# ESP32.net
KiCad netlist of a schematic drawn in Altium Designer
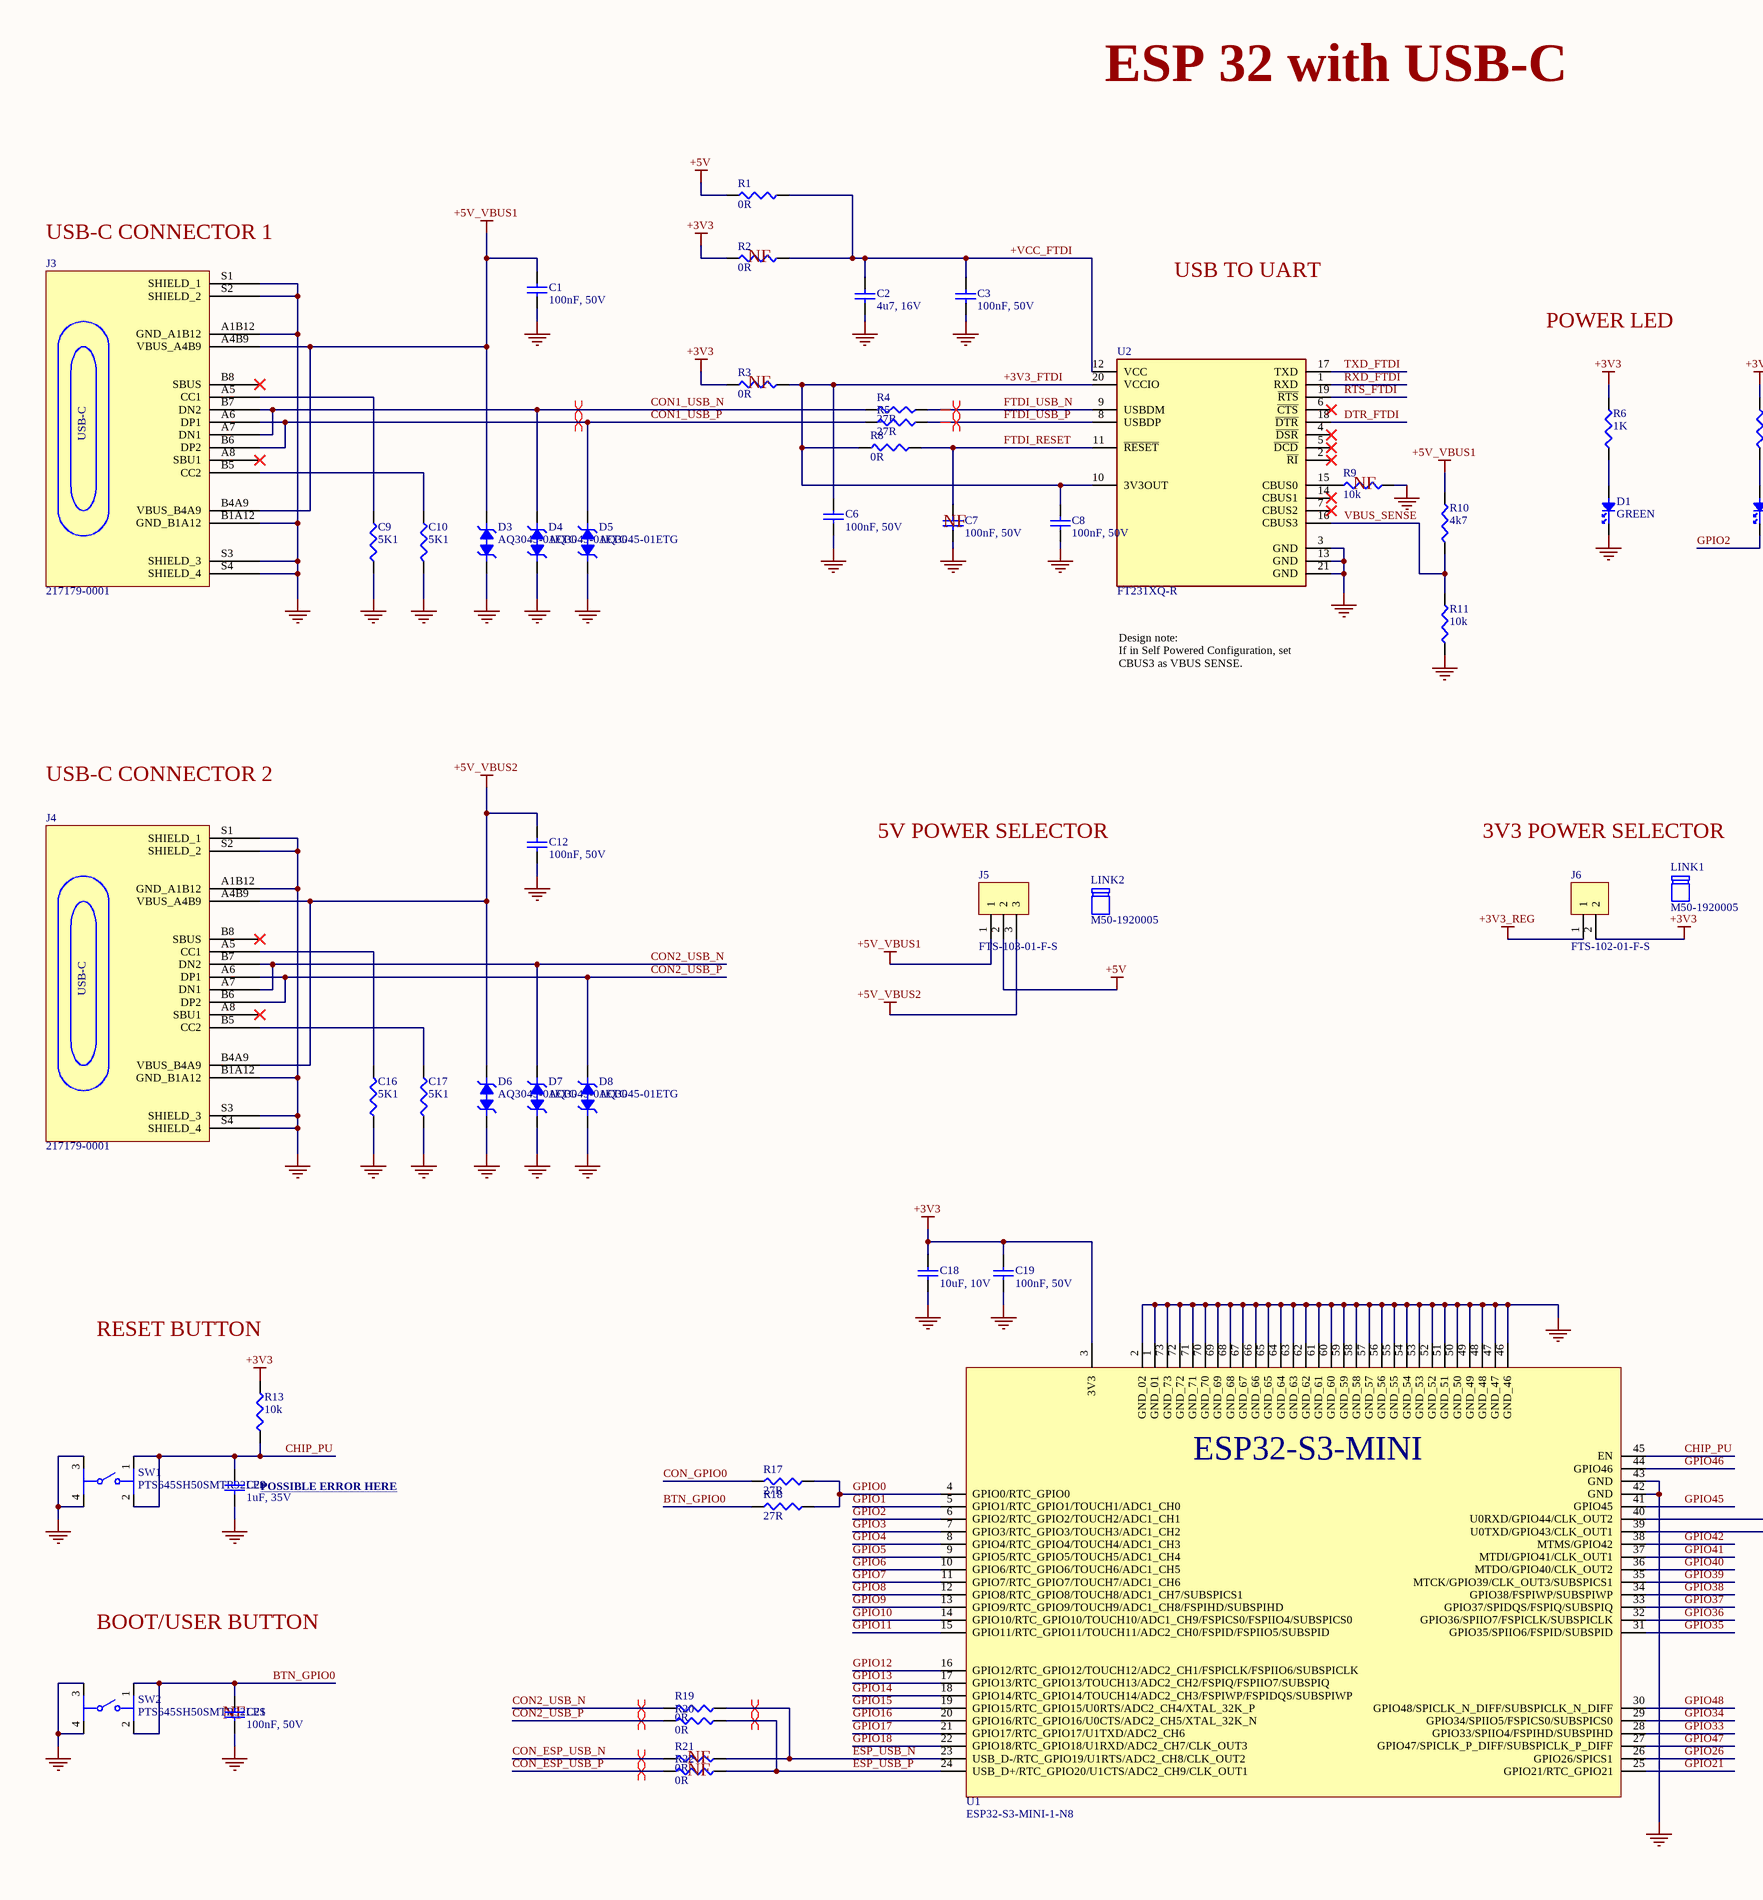
[diagram p0: ESP32.SchDoc, left]
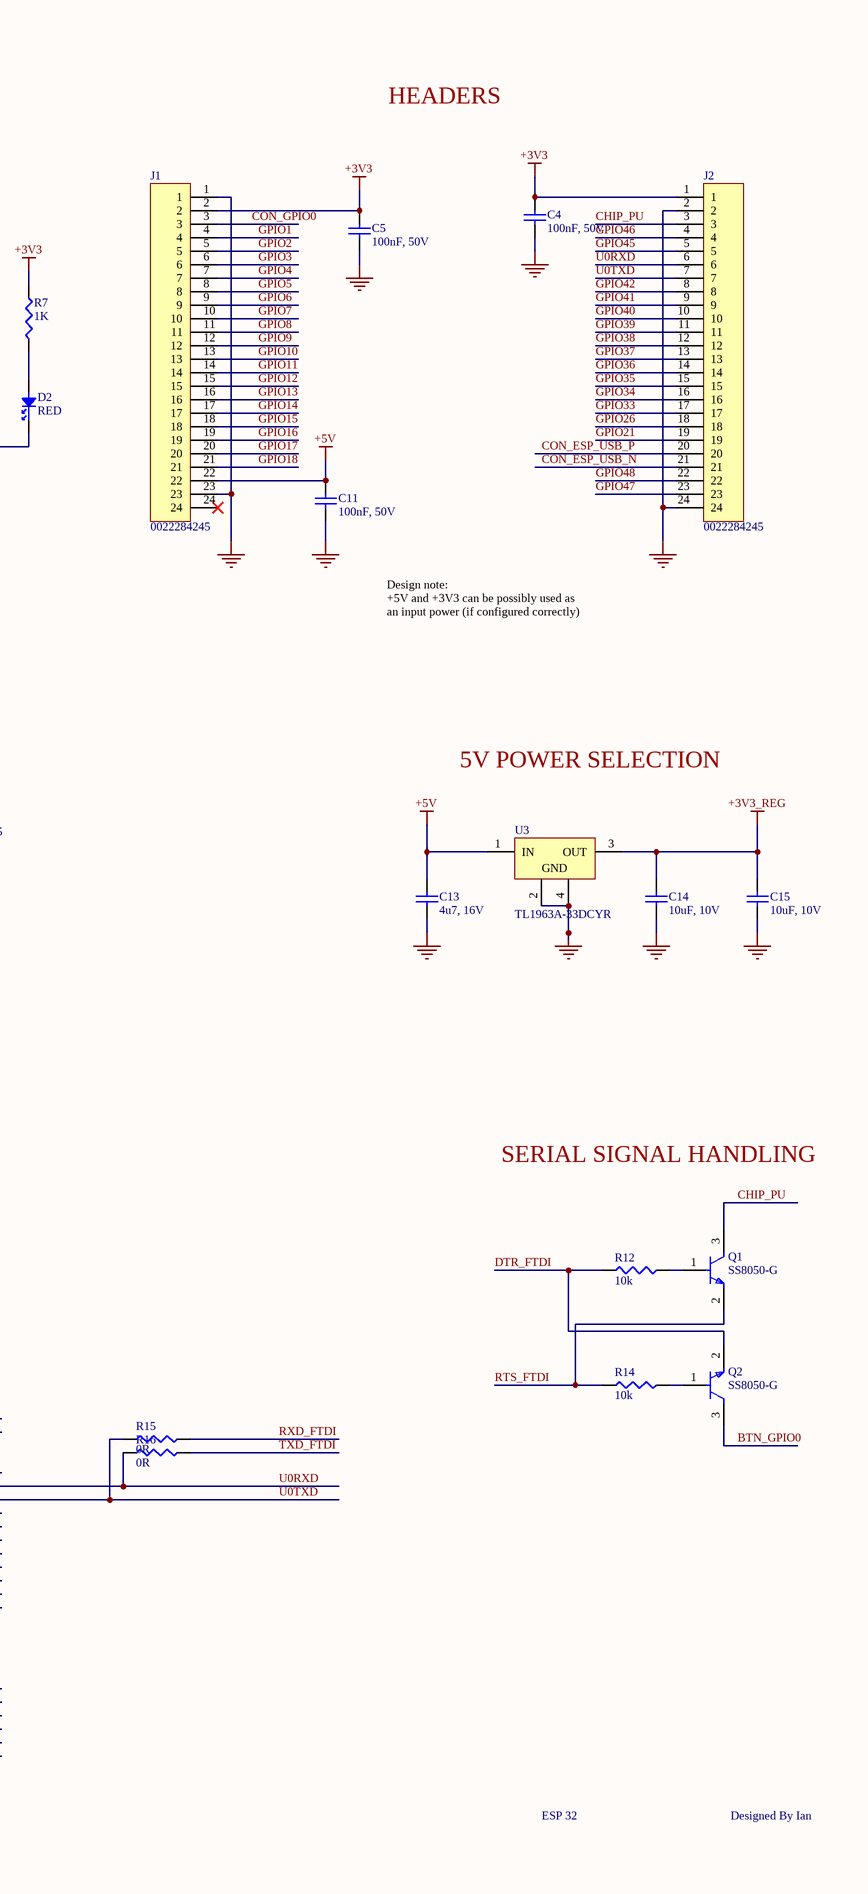
[diagram p1: ESP32.SchDoc, right]

(export (version "E")
  (design (tool "Eeschema 10.0.6"))
  (components
    (comp (ref "C1")
      (value "100nF, 50V")
      (footprint "CAPC1005X55N")
      (description "CAP CER 0.1UF 50V X7R 0402")
      (fields
        (field (name "MANUFACTURER") "Samsung")
        (field (name "MANUFACTURER PART NUMBER") "CL05B104KB54PNC")
      )
      (libsource (lib "Schlib1") (part "CL05B104KB54PNC"))
    )
    (comp (ref "C2")
      (value "4u7, 16V")
      (footprint "CAPC1005X55N")
      (description "CAP CER 4.7UF 16V X5R 0402")
      (fields
        (field (name "MANUFACTURER") "Samsung")
        (field (name "MANUFACTURER PART NUMBER") "CL05A475MO5NUNC")
      )
      (libsource (lib "Schlib1") (part "CL05A475MO5NUNC"))
    )
    (comp (ref "C3")
      (value "100nF, 50V")
      (footprint "CAPC1005X55N")
      (description "CAP CER 0.1UF 50V X7R 0402")
      (fields
        (field (name "MANUFACTURER") "Samsung")
        (field (name "MANUFACTURER PART NUMBER") "CL05B104KB54PNC")
      )
      (libsource (lib "Schlib1") (part "CL05B104KB54PNC"))
    )
    (comp (ref "C4")
      (value "100nF, 50V")
      (footprint "CAPC1005X55N")
      (description "CAP CER 0.1UF 50V X7R 0402")
      (fields
        (field (name "MANUFACTURER") "Samsung")
        (field (name "MANUFACTURER PART NUMBER") "CL05B104KB54PNC")
      )
      (libsource (lib "Schlib1") (part "CL05B104KB54PNC"))
    )
    (comp (ref "C5")
      (value "100nF, 50V")
      (footprint "CAPC1005X55N")
      (description "CAP CER 0.1UF 50V X7R 0402")
      (fields
        (field (name "MANUFACTURER") "Samsung")
        (field (name "MANUFACTURER PART NUMBER") "CL05B104KB54PNC")
      )
      (libsource (lib "Schlib1") (part "CL05B104KB54PNC"))
    )
    (comp (ref "C6")
      (value "100nF, 50V")
      (footprint "CAPC1005X55N")
      (description "CAP CER 0.1UF 50V X7R 0402")
      (fields
        (field (name "MANUFACTURER") "Samsung")
        (field (name "MANUFACTURER PART NUMBER") "CL05B104KB54PNC")
      )
      (libsource (lib "Schlib1") (part "CL05B104KB54PNC"))
    )
    (comp (ref "C7")
      (value "100nF, 50V")
      (footprint "CAPC1005X55N")
      (description "CAP CER 0.1UF 50V X7R 0402")
      (fields
        (field (name "MANUFACTURER") "Samsung")
        (field (name "MANUFACTURER PART NUMBER") "CL05B104KB54PNC")
      )
      (libsource (lib "Schlib1") (part "CL05B104KB54PNC"))
    )
    (comp (ref "C8")
      (value "100nF, 50V")
      (footprint "CAPC1005X55N")
      (description "CAP CER 0.1UF 50V X7R 0402")
      (fields
        (field (name "MANUFACTURER") "Samsung")
        (field (name "MANUFACTURER PART NUMBER") "CL05B104KB54PNC")
      )
      (libsource (lib "Schlib1") (part "CL05B104KB54PNC"))
    )
    (comp (ref "C9")
      (value "5K1")
      (footprint "RESC1005X37N")
      (description "5.1 kOhms ±1% 0.063W, 1/16W Chip Resistor 0402")
      (fields
        (field (name "MANUFACTURER") "Yageo")
        (field (name "MANUFACTURER PART NUMBER") "AC0402FR-075K1L")
      )
      (libsource (lib "Schlib1") (part "AC0402FR-075K1L"))
    )
    (comp (ref "C10")
      (value "5K1")
      (footprint "RESC1005X37N")
      (description "5.1 kOhms ±1% 0.063W, 1/16W Chip Resistor 0402")
      (fields
        (field (name "MANUFACTURER") "Yageo")
        (field (name "MANUFACTURER PART NUMBER") "AC0402FR-075K1L")
      )
      (libsource (lib "Schlib1") (part "AC0402FR-075K1L"))
    )
    (comp (ref "C11")
      (value "100nF, 50V")
      (footprint "CAPC1005X55N")
      (description "CAP CER 0.1UF 50V X7R 0402")
      (fields
        (field (name "MANUFACTURER") "Samsung")
        (field (name "MANUFACTURER PART NUMBER") "CL05B104KB54PNC")
      )
      (libsource (lib "Schlib1") (part "CL05B104KB54PNC"))
    )
    (comp (ref "C12")
      (value "100nF, 50V")
      (footprint "CAPC1005X55N")
      (description "CAP CER 0.1UF 50V X7R 0402")
      (fields
        (field (name "MANUFACTURER") "Samsung")
        (field (name "MANUFACTURER PART NUMBER") "CL05B104KB54PNC")
      )
      (libsource (lib "Schlib1") (part "CL05B104KB54PNC"))
    )
    (comp (ref "C13")
      (value "4u7, 16V")
      (footprint "CAPC1005X55N")
      (description "CAP CER 4.7UF 16V X5R 0402")
      (fields
        (field (name "MANUFACTURER") "Samsung")
        (field (name "MANUFACTURER PART NUMBER") "CL05A475MO5NUNC")
      )
      (libsource (lib "Schlib1") (part "CL05A475MO5NUNC"))
    )
    (comp (ref "C14")
      (value "10uF, 10V")
      (footprint "CAPC1005X55N")
      (description "CAP CER 10UF 10V X5R 0402")
      (fields
        (field (name "MANUFACTURER") "Samsung")
        (field (name "MANUFACTURER PART NUMBER") "CL05A106MP5NUNC")
      )
      (libsource (lib "Schlib1") (part "CL05A106MP5NUNC"))
    )
    (comp (ref "C15")
      (value "10uF, 10V")
      (footprint "CAPC1005X55N")
      (description "CAP CER 10UF 10V X5R 0402")
      (fields
        (field (name "MANUFACTURER") "Samsung")
        (field (name "MANUFACTURER PART NUMBER") "CL05A106MP5NUNC")
      )
      (libsource (lib "Schlib1") (part "CL05A106MP5NUNC"))
    )
    (comp (ref "C16")
      (value "5K1")
      (footprint "RESC1005X37N")
      (description "5.1 kOhms ±1% 0.063W, 1/16W Chip Resistor 0402")
      (fields
        (field (name "MANUFACTURER") "Yageo")
        (field (name "MANUFACTURER PART NUMBER") "AC0402FR-075K1L")
      )
      (libsource (lib "Schlib1") (part "AC0402FR-075K1L"))
    )
    (comp (ref "C17")
      (value "5K1")
      (footprint "RESC1005X37N")
      (description "5.1 kOhms ±1% 0.063W, 1/16W Chip Resistor 0402")
      (fields
        (field (name "MANUFACTURER") "Yageo")
        (field (name "MANUFACTURER PART NUMBER") "AC0402FR-075K1L")
      )
      (libsource (lib "Schlib1") (part "AC0402FR-075K1L"))
    )
    (comp (ref "C18")
      (value "10uF, 10V")
      (footprint "CAPC1005X55N")
      (description "CAP CER 10UF 10V X5R 0402")
      (fields
        (field (name "MANUFACTURER") "Samsung")
        (field (name "MANUFACTURER PART NUMBER") "CL05A106MP5NUNC")
      )
      (libsource (lib "Schlib1") (part "CL05A106MP5NUNC"))
    )
    (comp (ref "C19")
      (value "100nF, 50V")
      (footprint "CAPC1005X55N")
      (description "CAP CER 0.1UF 50V X7R 0402")
      (fields
        (field (name "MANUFACTURER") "Samsung")
        (field (name "MANUFACTURER PART NUMBER") "CL05B104KB54PNC")
      )
      (libsource (lib "Schlib1") (part "CL05B104KB54PNC"))
    )
    (comp (ref "C20")
      (value "1uF, 35V")
      (footprint "CAPC1005X55N")
      (description "1 µF ±10% 35V Ceramic Capacitor X5R 0402 (1005 Metric)")
      (fields
        (field (name "MANUFACTURER") "Murata")
        (field (name "MANUFACTURER PART NUMBER") "GRM155R6YA105KE11D")
      )
      (libsource (lib "Schlib1") (part "GRM155R6YA105KE11D"))
    )
    (comp (ref "C21")
      (value "100nF, 50V")
      (footprint "CAPC1005X55N")
      (description "CAP CER 0.1UF 50V X7R 0402")
      (fields
        (field (name "MANUFACTURER") "Samsung")
        (field (name "MANUFACTURER PART NUMBER") "CL05B104KB54PNC")
      )
      (libsource (lib "Schlib1") (part "CL05B104KB54PNC"))
    )
    (comp (ref "D1")
      (value "GREEN")
      (footprint "LED0402G")
      (description "LED YLW-GRN 0402 SMD")
      (fields
        (field (name "MANUFACTURER") "Vishay")
        (field (name "MANUFACTURER PART NUMBER") "VLMG1500-GS08")
      )
      (libsource (lib "Schlib1") (part "VLMG1500-GS08"))
    )
    (comp (ref "D2")
      (value "RED")
      (footprint "LED0402R")
      (description "LED RED 0402 SMD")
      (fields
        (field (name "MANUFACTURER") "Vishay")
        (field (name "MANUFACTURER PART NUMBER") "VLMS1500-GS08")
      )
      (libsource (lib "Schlib1") (part "VLMS1500-GS08"))
    )
    (comp (ref "D3")
      (value "AQ3045-01ETG")
      (footprint "SOD882")
      (description "TVS DIODE 5.3VWM 12VC SOD882")
      (fields (field (name "MANUFACTURER") "Littelfuse") (field (name "LCSC PART NUMBER") "C3710326"))
      (libsource (lib "Schlib1") (part "AQ3045-01ETG"))
    )
    (comp (ref "D4")
      (value "AQ3045-01ETG")
      (footprint "SOD882")
      (description "TVS DIODE 5.3VWM 12VC SOD882")
      (fields (field (name "MANUFACTURER") "Littelfuse") (field (name "LCSC PART NUMBER") "C3710326"))
      (libsource (lib "Schlib1") (part "AQ3045-01ETG"))
    )
    (comp (ref "D5")
      (value "AQ3045-01ETG")
      (footprint "SOD882")
      (description "TVS DIODE 5.3VWM 12VC SOD882")
      (fields (field (name "MANUFACTURER") "Littelfuse") (field (name "LCSC PART NUMBER") "C3710326"))
      (libsource (lib "Schlib1") (part "AQ3045-01ETG"))
    )
    (comp (ref "D6")
      (value "AQ3045-01ETG")
      (footprint "SOD882")
      (description "TVS DIODE 5.3VWM 12VC SOD882")
      (fields (field (name "MANUFACTURER") "Littelfuse") (field (name "LCSC PART NUMBER") "C3710326"))
      (libsource (lib "Schlib1") (part "AQ3045-01ETG"))
    )
    (comp (ref "D7")
      (value "AQ3045-01ETG")
      (footprint "SOD882")
      (description "TVS DIODE 5.3VWM 12VC SOD882")
      (fields (field (name "MANUFACTURER") "Littelfuse") (field (name "LCSC PART NUMBER") "C3710326"))
      (libsource (lib "Schlib1") (part "AQ3045-01ETG"))
    )
    (comp (ref "D8")
      (value "AQ3045-01ETG")
      (footprint "SOD882")
      (description "TVS DIODE 5.3VWM 12VC SOD882")
      (fields (field (name "MANUFACTURER") "Littelfuse") (field (name "LCSC PART NUMBER") "C3710326"))
      (libsource (lib "Schlib1") (part "AQ3045-01ETG"))
    )
    (comp (ref "J1")
      (value "0022284245")
      (footprint "HDR_1X24_2.54mm")
      (description "CONN HEADER VERT 24POS 2.54MM")
      (fields (field (name "MANUFACTURER") "Molex") (field (name "LCSC PART NUMBER") "C7145888"))
      (libsource (lib "Schlib1") (part "0022284245"))
    )
    (comp (ref "J2")
      (value "0022284245")
      (footprint "HDR_1X24_2.54mm")
      (description "CONN HEADER VERT 24POS 2.54MM")
      (fields (field (name "MANUFACTURER") "Molex") (field (name "LCSC PART NUMBER") "C7145888"))
      (libsource (lib "") (part "0022284245_1"))
    )
    (comp (ref "J3")
      (value "217179-0001")
      (footprint "FP-2171790001-MFG")
      (description "CONN RCP USB2.0 TYP C 24P SMD RA")
      (fields (field (name "MANUFACTURER") "Molex") (field (name "LCSC PART NUMBER") "C3197684"))
      (libsource (lib "Schlib1") (part "217179-0001"))
    )
    (comp (ref "J4")
      (value "217179-0001")
      (footprint "FP-2171790001-MFG")
      (description "CONN RCP USB2.0 TYP C 24P SMD RA")
      (fields (field (name "MANUFACTURER") "Molex") (field (name "LCSC PART NUMBER") "C3197684"))
      (libsource (lib "Schlib1") (part "217179-0001"))
    )
    (comp (ref "J5")
      (value "FTS-103-01-F-S")
      (footprint "HDR_1X3_1.27MM")
      (description "CONN HEADER VERT 3POS 1.27MM")
      (fields (field (name "MANUFACTURER") "Samtec") (field (name "LCSC PART NUMBER") "C3333578"))
      (libsource (lib "Schlib1") (part "FTS-103-01-F-S"))
    )
    (comp (ref "J6")
      (value "FTS-102-01-F-S")
      (footprint "HDR_1X2_1.27MM")
      (description "CONN HEADER VERT 2POS 1.27MM")
      (fields (field (name "MANUFACTURER") "Samtec") (field (name "LCSC PART NUMBER") "C6045317"))
      (libsource (lib "Schlib1") (part "FTS-102-01-F-S"))
    )
    (comp (ref "LINK1")
      (value "M50-1920005")
      (description "CONN SHUNT 1.27MM RED")
      (fields (field (name "MANUFACTURER") "Harwin") (field (name "LCSC PART NUMBER") "C6985646"))
      (libsource (lib "Schlib1") (part "M50-1920005"))
    )
    (comp (ref "LINK2")
      (value "M50-1920005")
      (description "CONN SHUNT 1.27MM RED")
      (fields (field (name "MANUFACTURER") "Harwin") (field (name "LCSC PART NUMBER") "C6985646"))
      (libsource (lib "Schlib1") (part "M50-1920005"))
    )
    (comp (ref "Q1")
      (value "SS8050-G")
      (footprint "FP-SS8050-G-IPC_B")
      (description "TRANS NPN 25V 1.5A SOT23-3")
      (fields (field (name "MANUFACTURER") "Comchip") (field (name "LCSC PART NUMBER") "C3199946"))
      (libsource (lib "Schlib1") (part "SS8050-G"))
    )
    (comp (ref "Q2")
      (value "SS8050-G")
      (footprint "FP-SS8050-G-IPC_B")
      (description "TRANS NPN 25V 1.5A SOT23-3")
      (fields (field (name "MANUFACTURER") "Comchip") (field (name "LCSC PART NUMBER") "C3199946"))
      (libsource (lib "Schlib1") (part "SS8050-G"))
    )
    (comp (ref "R1")
      (value "0R")
      (footprint "RESC1005X37N")
      (description "RES 0 OHM JUMPER 1/16W 0402")
      (fields
        (field (name "MANUFACTURER") "Yageo")
        (field (name "MANUFACTURER PART NUMBER") "RC0402JR-070RL")
      )
      (libsource (lib "Schlib1") (part "RC0402JR-070RL"))
    )
    (comp (ref "R2")
      (value "0R")
      (footprint "RESC1005X37N")
      (description "RES 0 OHM JUMPER 1/16W 0402")
      (fields
        (field (name "MANUFACTURER") "Yageo")
        (field (name "MANUFACTURER PART NUMBER") "RC0402JR-070RL")
      )
      (libsource (lib "Schlib1") (part "RC0402JR-070RL"))
    )
    (comp (ref "R3")
      (value "0R")
      (footprint "RESC1005X37N")
      (description "RES 0 OHM JUMPER 1/16W 0402")
      (fields
        (field (name "MANUFACTURER") "Yageo")
        (field (name "MANUFACTURER PART NUMBER") "RC0402JR-070RL")
      )
      (libsource (lib "Schlib1") (part "RC0402JR-070RL"))
    )
    (comp (ref "R4")
      (value "27R")
      (footprint "RESC1005X37N")
      (description "27 Ohms ±1% 0.063W, 1/16W Chip Resistor 0402")
      (fields
        (field (name "MANUFACTURER") "Yageo")
        (field (name "MANUFACTURER PART NUMBER") "RC0402FR-0727RL")
      )
      (libsource (lib "Schlib1") (part "RC0402FR-0727RL"))
    )
    (comp (ref "R5")
      (value "27R")
      (footprint "RESC1005X37N")
      (description "27 Ohms ±1% 0.063W, 1/16W Chip Resistor 0402")
      (fields
        (field (name "MANUFACTURER") "Yageo")
        (field (name "MANUFACTURER PART NUMBER") "RC0402FR-0727RL")
      )
      (libsource (lib "Schlib1") (part "RC0402FR-0727RL"))
    )
    (comp (ref "R6")
      (value "1K")
      (footprint "RESC1005X37N")
      (description "RES 1K OHM 1% 1/16W 0402")
      (fields
        (field (name "MANUFACTURER") "Yageo")
        (field (name "MANUFACTURER PART NUMBER") "RC0402FR-071KL")
      )
      (libsource (lib "Schlib1") (part "RC0402FR-071KL"))
    )
    (comp (ref "R7")
      (value "1K")
      (footprint "RESC1005X37N")
      (description "RES 1K OHM 1% 1/16W 0402")
      (fields
        (field (name "MANUFACTURER") "Yageo")
        (field (name "MANUFACTURER PART NUMBER") "RC0402FR-071KL")
      )
      (libsource (lib "Schlib1") (part "RC0402FR-071KL"))
    )
    (comp (ref "R8")
      (value "0R")
      (footprint "RESC1005X37N")
      (description "RES 0 OHM JUMPER 1/16W 0402")
      (fields
        (field (name "MANUFACTURER") "Yageo")
        (field (name "MANUFACTURER PART NUMBER") "RC0402JR-070RL")
      )
      (libsource (lib "Schlib1") (part "RC0402JR-070RL"))
    )
    (comp (ref "R9")
      (value "10k")
      (footprint "RESC1005X37N")
      (description "RES SMD 10K OHM 1% 1/16W 0402")
      (fields
        (field (name "MANUFACTURER") "Yageo")
        (field (name "MANUFACTURER PART NUMBER") "AC0402FR-0710KL")
      )
      (libsource (lib "Schlib1") (part "AC0402FR-0710KL"))
    )
    (comp (ref "R10")
      (value "4k7")
      (footprint "RESC1005X37N")
      (description "RES 4.7K OHM 5% 1/16W 0402")
      (fields
        (field (name "MANUFACTURER") "Yageo")
        (field (name "MANUFACTURER PART NUMBER") "RC0402JR-074K7L")
      )
      (libsource (lib "Schlib1") (part "RC0402JR-074K7L"))
    )
    (comp (ref "R11")
      (value "10k")
      (footprint "RESC1005X37N")
      (description "RES SMD 10K OHM 1% 1/16W 0402")
      (fields
        (field (name "MANUFACTURER") "Yageo")
        (field (name "MANUFACTURER PART NUMBER") "AC0402FR-0710KL")
      )
      (libsource (lib "Schlib1") (part "AC0402FR-0710KL"))
    )
    (comp (ref "R12")
      (value "10k")
      (footprint "RESC1005X37N")
      (description "RES SMD 10K OHM 1% 1/16W 0402")
      (fields
        (field (name "MANUFACTURER") "Yageo")
        (field (name "MANUFACTURER PART NUMBER") "AC0402FR-0710KL")
      )
      (libsource (lib "Schlib1") (part "AC0402FR-0710KL"))
    )
    (comp (ref "R13")
      (value "10k")
      (footprint "RESC1005X37N")
      (description "RES SMD 10K OHM 1% 1/16W 0402")
      (fields
        (field (name "MANUFACTURER") "Yageo")
        (field (name "MANUFACTURER PART NUMBER") "AC0402FR-0710KL")
      )
      (libsource (lib "Schlib1") (part "AC0402FR-0710KL"))
    )
    (comp (ref "R14")
      (value "10k")
      (footprint "RESC1005X37N")
      (description "RES SMD 10K OHM 1% 1/16W 0402")
      (fields
        (field (name "MANUFACTURER") "Yageo")
        (field (name "MANUFACTURER PART NUMBER") "AC0402FR-0710KL")
      )
      (libsource (lib "Schlib1") (part "AC0402FR-0710KL"))
    )
    (comp (ref "R15")
      (value "0R")
      (footprint "RESC1005X37N")
      (description "RES 0 OHM JUMPER 1/16W 0402")
      (fields
        (field (name "MANUFACTURER") "Yageo")
        (field (name "MANUFACTURER PART NUMBER") "RC0402JR-070RL")
      )
      (libsource (lib "Schlib1") (part "RC0402JR-070RL"))
    )
    (comp (ref "R16")
      (value "0R")
      (footprint "RESC1005X37N")
      (description "RES 0 OHM JUMPER 1/16W 0402")
      (fields
        (field (name "MANUFACTURER") "Yageo")
        (field (name "MANUFACTURER PART NUMBER") "RC0402JR-070RL")
      )
      (libsource (lib "Schlib1") (part "RC0402JR-070RL"))
    )
    (comp (ref "R17")
      (value "27R")
      (footprint "RESC1005X37N")
      (description "27 Ohms ±1% 0.063W, 1/16W Chip Resistor 0402")
      (fields
        (field (name "MANUFACTURER") "Yageo")
        (field (name "MANUFACTURER PART NUMBER") "RC0402FR-0727RL")
      )
      (libsource (lib "Schlib1") (part "RC0402FR-0727RL"))
    )
    (comp (ref "R18")
      (value "27R")
      (footprint "RESC1005X37N")
      (description "27 Ohms ±1% 0.063W, 1/16W Chip Resistor 0402")
      (fields
        (field (name "MANUFACTURER") "Yageo")
        (field (name "MANUFACTURER PART NUMBER") "RC0402FR-0727RL")
      )
      (libsource (lib "Schlib1") (part "RC0402FR-0727RL"))
    )
    (comp (ref "R19")
      (value "0R")
      (footprint "RESC1005X37N")
      (description "RES 0 OHM JUMPER 1/16W 0402")
      (fields
        (field (name "MANUFACTURER") "Yageo")
        (field (name "MANUFACTURER PART NUMBER") "RC0402JR-070RL")
      )
      (libsource (lib "Schlib1") (part "RC0402JR-070RL"))
    )
    (comp (ref "R20")
      (value "0R")
      (footprint "RESC1005X37N")
      (description "RES 0 OHM JUMPER 1/16W 0402")
      (fields
        (field (name "MANUFACTURER") "Yageo")
        (field (name "MANUFACTURER PART NUMBER") "RC0402JR-070RL")
      )
      (libsource (lib "Schlib1") (part "RC0402JR-070RL"))
    )
    (comp (ref "R21")
      (value "0R")
      (footprint "RESC1005X37N")
      (description "RES 0 OHM JUMPER 1/16W 0402")
      (fields
        (field (name "MANUFACTURER") "Yageo")
        (field (name "MANUFACTURER PART NUMBER") "RC0402JR-070RL")
      )
      (libsource (lib "Schlib1") (part "RC0402JR-070RL"))
    )
    (comp (ref "R22")
      (value "0R")
      (footprint "RESC1005X37N")
      (description "RES 0 OHM JUMPER 1/16W 0402")
      (fields
        (field (name "MANUFACTURER") "Yageo")
        (field (name "MANUFACTURER PART NUMBER") "RC0402JR-070RL")
      )
      (libsource (lib "Schlib1") (part "RC0402JR-070RL"))
    )
    (comp (ref "SW1")
      (value "PTS645SH50SMTR92LFS")
      (footprint "FP-PTS645SH50SMTR92LFS-MFG")
      (description "Tactile Switch SPST-NO Top Actuated Surface Mount")
      (fields (field (name "MANUFACTURER") "ITT C&K") (field (name "LCSC PART NUMBER") "C221869"))
      (libsource (lib "Schlib1") (part "PTS645SH50SMTR92LFS"))
    )
    (comp (ref "SW2")
      (value "PTS645SH50SMTR92LFS")
      (footprint "FP-PTS645SH50SMTR92LFS-MFG")
      (description "Tactile Switch SPST-NO Top Actuated Surface Mount")
      (fields (field (name "MANUFACTURER") "ITT C&K") (field (name "LCSC PART NUMBER") "C221869"))
      (libsource (lib "Schlib1") (part "PTS645SH50SMTR92LFS"))
    )
    (comp (ref "U1")
      (value "ESP32-S3-MINI-1-N8")
      (footprint "XCVR_ESP32-S3-MINI-1-N8")
      (description "SMD module, ESP32-S3FN8, 8 MB SPI flash, PCB antenna")
      (fields (field (name "MANUFACTURER") "Espressif Systems") (field (name "LCSC PART NUMBER") "C2913206"))
      (libsource (lib "Schlib1") (part "ESP32-S3-MINI-1-N8"))
    )
    (comp (ref "U2")
      (value "FT231XQ-R")
      (footprint "FP-QFN-20-IPC_B")
      (description "IC USB SERIAL FULL UART 20QFN")
      (fields (field (name "MANUFACTURER") "FTDI") (field (name "LCSC PART NUMBER") "C132159"))
      (libsource (lib "Schlib1") (part "FT231XQ-R"))
    )
    (comp (ref "U3")
      (value "TL1963A-33DCYR")
      (footprint "DCY0004A_N")
      (description "IC REG LINEAR 3.3V 1.5A SOT223-4")
      (fields (field (name "MANUFACTURER") "Texas Instruments") (field (name "LCSC PART NUMBER") "C181262"))
      (libsource (lib "Schlib1") (part "TL1963A-33DCYR"))
    )
  )
  (nets
    (net (code "1") (name "+3V3") (class "Default")
      (node (ref "C18") (pin "2") (pinfunction "2_2") (pintype "passive"))
      (node (ref "C19") (pin "2") (pinfunction "2_2") (pintype "passive"))
      (node (ref "C4") (pin "2") (pinfunction "2_2") (pintype "passive"))
      (node (ref "C5") (pin "2") (pinfunction "2_2") (pintype "passive"))
      (node (ref "J1") (pin "2") (pinfunction "2_2") (pintype "passive"))
      (node (ref "J2") (pin "1") (pinfunction "1_1") (pintype "passive"))
      (node (ref "J6") (pin "2") (pinfunction "2_2") (pintype "passive"))
      (node (ref "R13") (pin "2") (pinfunction "2_2") (pintype "passive"))
      (node (ref "R2") (pin "1") (pinfunction "1_1") (pintype "passive"))
      (node (ref "R3") (pin "1") (pinfunction "1_1") (pintype "passive"))
      (node (ref "R6") (pin "2") (pinfunction "2_2") (pintype "passive"))
      (node (ref "R7") (pin "2") (pinfunction "2_2") (pintype "passive"))
      (node (ref "U1") (pin "3") (pinfunction "3V3_3") (pintype "passive"))
    )
    (net (code "2") (name "+3V3_REG") (class "Default")
      (node (ref "C14") (pin "2") (pinfunction "2_2") (pintype "passive"))
      (node (ref "C15") (pin "2") (pinfunction "2_2") (pintype "passive"))
      (node (ref "J6") (pin "1") (pinfunction "1_1") (pintype "passive"))
      (node (ref "U3") (pin "3") (pinfunction "OUT_3") (pintype "power_in"))
    )
    (net (code "3") (name "+5V") (class "Default")
      (node (ref "C11") (pin "2") (pinfunction "2_2") (pintype "passive"))
      (node (ref "C13") (pin "2") (pinfunction "2_2") (pintype "passive"))
      (node (ref "J1") (pin "22") (pinfunction "22_22") (pintype "passive"))
      (node (ref "J5") (pin "2") (pinfunction "2_2") (pintype "passive"))
      (node (ref "R1") (pin "1") (pinfunction "1_1") (pintype "passive"))
      (node (ref "U3") (pin "1") (pinfunction "IN_1") (pintype "power_in"))
    )
    (net (code "4") (name "+5V_VBUS1") (class "Default")
      (node (ref "C1") (pin "2") (pinfunction "2_2") (pintype "passive"))
      (node (ref "D3") (pin "2") (pinfunction "2_2") (pintype "passive"))
      (node (ref "J3") (pin "A4B9") (pinfunction "VBUS_A4B9_A4B9") (pintype "passive"))
      (node (ref "J3") (pin "B4A9") (pinfunction "VBUS_B4A9_B4A9") (pintype "passive"))
      (node (ref "J5") (pin "1") (pinfunction "1_1") (pintype "passive"))
      (node (ref "R10") (pin "2") (pinfunction "2_2") (pintype "passive"))
    )
    (net (code "5") (name "+5V_VBUS2") (class "Default")
      (node (ref "C12") (pin "2") (pinfunction "2_2") (pintype "passive"))
      (node (ref "D6") (pin "2") (pinfunction "2_2") (pintype "passive"))
      (node (ref "J4") (pin "A4B9") (pinfunction "VBUS_A4B9_A4B9") (pintype "passive"))
      (node (ref "J4") (pin "B4A9") (pinfunction "VBUS_B4A9_B4A9") (pintype "passive"))
      (node (ref "J5") (pin "3") (pinfunction "3_3") (pintype "passive"))
    )
    (net (code "6") (name "/+3V3_FTDI") (class "Default")
      (node (ref "C6") (pin "2") (pinfunction "2_2") (pintype "passive"))
      (node (ref "C8") (pin "2") (pinfunction "2_2") (pintype "passive"))
      (node (ref "R3") (pin "2") (pinfunction "2_2") (pintype "passive"))
      (node (ref "R8") (pin "1") (pinfunction "1_1") (pintype "passive"))
      (node (ref "U2") (pin "10") (pinfunction "3V3OUT_10") (pintype "passive"))
      (node (ref "U2") (pin "20") (pinfunction "VCCIO_20") (pintype "passive"))
    )
    (net (code "7") (name "/+VCC_FTDI") (class "Default")
      (node (ref "C2") (pin "2") (pinfunction "2_2") (pintype "passive"))
      (node (ref "C3") (pin "2") (pinfunction "2_2") (pintype "passive"))
      (node (ref "R1") (pin "2") (pinfunction "2_2") (pintype "passive"))
      (node (ref "R2") (pin "2") (pinfunction "2_2") (pintype "passive"))
      (node (ref "U2") (pin "12") (pinfunction "VCC_12") (pintype "passive"))
    )
    (net (code "8") (name "/BTN_GPIO0") (class "Default")
      (node (ref "C21") (pin "2") (pinfunction "2_2") (pintype "passive"))
      (node (ref "Q2") (pin "3") (pinfunction "C_3") (pintype "passive"))
      (node (ref "R18") (pin "1") (pinfunction "1_1") (pintype "passive"))
      (node (ref "SW2") (pin "1") (pinfunction "1_1") (pintype "passive"))
      (node (ref "SW2") (pin "2") (pinfunction "2_2") (pintype "passive"))
    )
    (net (code "9") (name "/CHIP_PU") (class "Default")
      (node (ref "C20") (pin "2") (pinfunction "2_2") (pintype "passive"))
      (node (ref "J2") (pin "3") (pinfunction "3_3") (pintype "passive"))
      (node (ref "Q1") (pin "3") (pinfunction "C_3") (pintype "passive"))
      (node (ref "R13") (pin "1") (pinfunction "1_1") (pintype "passive"))
      (node (ref "SW1") (pin "1") (pinfunction "1_1") (pintype "passive"))
      (node (ref "SW1") (pin "2") (pinfunction "2_2") (pintype "passive"))
      (node (ref "U1") (pin "45") (pinfunction "EN_45") (pintype "passive"))
    )
    (net (code "10") (name "/CON1_USB_N") (class "Default")
      (node (ref "D4") (pin "2") (pinfunction "2_2") (pintype "passive"))
      (node (ref "J3") (pin "A7") (pinfunction "DN1_A7") (pintype "passive"))
      (node (ref "J3") (pin "B7") (pinfunction "DN2_B7") (pintype "passive"))
      (node (ref "R4") (pin "1") (pinfunction "1_1") (pintype "passive"))
    )
    (net (code "11") (name "/CON1_USB_P") (class "Default")
      (node (ref "D5") (pin "2") (pinfunction "2_2") (pintype "passive"))
      (node (ref "J3") (pin "A6") (pinfunction "DP1_A6") (pintype "passive"))
      (node (ref "J3") (pin "B6") (pinfunction "DP2_B6") (pintype "passive"))
      (node (ref "R5") (pin "1") (pinfunction "1_1") (pintype "passive"))
    )
    (net (code "12") (name "/CON2_USB_N") (class "Default")
      (node (ref "D7") (pin "2") (pinfunction "2_2") (pintype "passive"))
      (node (ref "J4") (pin "A7") (pinfunction "DN1_A7") (pintype "passive"))
      (node (ref "J4") (pin "B7") (pinfunction "DN2_B7") (pintype "passive"))
      (node (ref "R19") (pin "1") (pinfunction "1_1") (pintype "passive"))
    )
    (net (code "13") (name "/CON2_USB_P") (class "Default")
      (node (ref "D8") (pin "2") (pinfunction "2_2") (pintype "passive"))
      (node (ref "J4") (pin "A6") (pinfunction "DP1_A6") (pintype "passive"))
      (node (ref "J4") (pin "B6") (pinfunction "DP2_B6") (pintype "passive"))
      (node (ref "R20") (pin "1") (pinfunction "1_1") (pintype "passive"))
    )
    (net (code "14") (name "/CON_ESP_USB_N") (class "Default")
      (node (ref "J2") (pin "21") (pinfunction "21_21") (pintype "passive"))
      (node (ref "R21") (pin "1") (pinfunction "1_1") (pintype "passive"))
    )
    (net (code "15") (name "/CON_ESP_USB_P") (class "Default")
      (node (ref "J2") (pin "20") (pinfunction "20_20") (pintype "passive"))
      (node (ref "R22") (pin "1") (pinfunction "1_1") (pintype "passive"))
    )
    (net (code "16") (name "/CON_GPIO0") (class "Default")
      (node (ref "J1") (pin "3") (pinfunction "3_3") (pintype "passive"))
      (node (ref "R17") (pin "1") (pinfunction "1_1") (pintype "passive"))
    )
    (net (code "17") (name "/DTR_FTDI") (class "Default")
      (node (ref "Q2") (pin "2") (pinfunction "E_2") (pintype "passive"))
      (node (ref "R12") (pin "2") (pinfunction "2_2") (pintype "passive"))
      (node (ref "U2") (pin "18") (pinfunction "~{DTR}_18") (pintype "passive"))
    )
    (net (code "18") (name "/ESP_USB_N") (class "Default")
      (node (ref "R19") (pin "2") (pinfunction "2_2") (pintype "passive"))
      (node (ref "R21") (pin "2") (pinfunction "2_2") (pintype "passive"))
      (node (ref "U1") (pin "23") (pinfunction "USB_D-/RTC_GPIO19/U1RTS/ADC2_CH8/CLK_OUT2_23") (pintype "passive"))
    )
    (net (code "19") (name "/ESP_USB_P") (class "Default")
      (node (ref "R20") (pin "2") (pinfunction "2_2") (pintype "passive"))
      (node (ref "R22") (pin "2") (pinfunction "2_2") (pintype "passive"))
      (node (ref "U1") (pin "24") (pinfunction "USB_D+/RTC_GPIO20/U1CTS/ADC2_CH9/CLK_OUT1_24") (pintype "passive"))
    )
    (net (code "20") (name "/FTDI_RESET") (class "Default")
      (node (ref "C7") (pin "2") (pinfunction "2_2") (pintype "passive"))
      (node (ref "R8") (pin "2") (pinfunction "2_2") (pintype "passive"))
      (node (ref "U2") (pin "11") (pinfunction "~{RESET}_11") (pintype "passive"))
    )
    (net (code "21") (name "/FTDI_USB_N") (class "Default")
      (node (ref "R4") (pin "2") (pinfunction "2_2") (pintype "passive"))
      (node (ref "U2") (pin "9") (pinfunction "USBDM_9") (pintype "passive"))
    )
    (net (code "22") (name "/FTDI_USB_P") (class "Default")
      (node (ref "R5") (pin "2") (pinfunction "2_2") (pintype "passive"))
      (node (ref "U2") (pin "8") (pinfunction "USBDP_8") (pintype "passive"))
    )
    (net (code "23") (name "/GPIO0") (class "Default")
      (node (ref "R17") (pin "2") (pinfunction "2_2") (pintype "passive"))
      (node (ref "R18") (pin "2") (pinfunction "2_2") (pintype "passive"))
      (node (ref "U1") (pin "4") (pinfunction "GPIO0/RTC_GPIO0_4") (pintype "passive"))
    )
    (net (code "24") (name "/GPIO1") (class "Default")
      (node (ref "J1") (pin "4") (pinfunction "4_4") (pintype "passive"))
      (node (ref "U1") (pin "5") (pinfunction "GPIO1/RTC_GPIO1/TOUCH1/ADC1_CH0_5") (pintype "passive"))
    )
    (net (code "25") (name "/GPIO2") (class "Default")
      (node (ref "D2") (pin "1") (pinfunction "1_1") (pintype "passive"))
      (node (ref "J1") (pin "5") (pinfunction "5_5") (pintype "passive"))
      (node (ref "U1") (pin "6") (pinfunction "GPIO2/RTC_GPIO2/TOUCH2/ADC1_CH1_6") (pintype "passive"))
    )
    (net (code "26") (name "/GPIO3") (class "Default")
      (node (ref "J1") (pin "6") (pinfunction "6_6") (pintype "passive"))
      (node (ref "U1") (pin "7") (pinfunction "GPIO3/RTC_GPIO3/TOUCH3/ADC1_CH2_7") (pintype "passive"))
    )
    (net (code "27") (name "/GPIO4") (class "Default")
      (node (ref "J1") (pin "7") (pinfunction "7_7") (pintype "passive"))
      (node (ref "U1") (pin "8") (pinfunction "GPIO4/RTC_GPIO4/TOUCH4/ADC1_CH3_8") (pintype "passive"))
    )
    (net (code "28") (name "/GPIO5") (class "Default")
      (node (ref "J1") (pin "8") (pinfunction "8_8") (pintype "passive"))
      (node (ref "U1") (pin "9") (pinfunction "GPIO5/RTC_GPIO5/TOUCH5/ADC1_CH4_9") (pintype "passive"))
    )
    (net (code "29") (name "/GPIO6") (class "Default")
      (node (ref "J1") (pin "9") (pinfunction "9_9") (pintype "passive"))
      (node (ref "U1") (pin "10") (pinfunction "GPIO6/RTC_GPIO6/TOUCH6/ADC1_CH5_10") (pintype "passive"))
    )
    (net (code "30") (name "/GPIO7") (class "Default")
      (node (ref "J1") (pin "10") (pinfunction "10_10") (pintype "passive"))
      (node (ref "U1") (pin "11") (pinfunction "GPIO7/RTC_GPIO7/TOUCH7/ADC1_CH6_11") (pintype "passive"))
    )
    (net (code "31") (name "/GPIO8") (class "Default")
      (node (ref "J1") (pin "11") (pinfunction "11_11") (pintype "passive"))
      (node (ref "U1") (pin "12") (pinfunction "GPIO8/RTC_GPIO8/TOUCH8/ADC1_CH7/SUBSPICS1_12") (pintype "passive"))
    )
    (net (code "32") (name "/GPIO9") (class "Default")
      (node (ref "J1") (pin "12") (pinfunction "12_12") (pintype "passive"))
      (node (ref "U1") (pin "13") (pinfunction "GPIO9/RTC_GPIO9/TOUCH9/ADC1_CH8/FSPIHD/SUBSPIHD_13") (pintype "passive"))
    )
    (net (code "33") (name "/GPIO10") (class "Default")
      (node (ref "J1") (pin "13") (pinfunction "13_13") (pintype "passive"))
      (node (ref "U1") (pin "14") (pinfunction "GPIO10/RTC_GPIO10/TOUCH10/ADC1_CH9/FSPICS0/FSPIIO4/SUBSPICS0_14") (pintype "passive"))
    )
    (net (code "34") (name "/GPIO11") (class "Default")
      (node (ref "J1") (pin "14") (pinfunction "14_14") (pintype "passive"))
      (node (ref "U1") (pin "15") (pinfunction "GPIO11/RTC_GPIO11/TOUCH11/ADC2_CH0/FSPID/FSPIIO5/SUBSPID_15") (pintype "passive"))
    )
    (net (code "35") (name "/GPIO12") (class "Default")
      (node (ref "J1") (pin "15") (pinfunction "15_15") (pintype "passive"))
      (node (ref "U1") (pin "16") (pinfunction "GPIO12/RTC_GPIO12/TOUCH12/ADC2_CH1/FSPICLK/FSPIIO6/SUBSPICLK_16") (pintype "passive"))
    )
    (net (code "36") (name "/GPIO13") (class "Default")
      (node (ref "J1") (pin "16") (pinfunction "16_16") (pintype "passive"))
      (node (ref "U1") (pin "17") (pinfunction "GPIO13/RTC_GPIO13/TOUCH13/ADC2_CH2/FSPIQ/FSPIIO7/SUBSPIQ_17") (pintype "passive"))
    )
    (net (code "37") (name "/GPIO14") (class "Default")
      (node (ref "J1") (pin "17") (pinfunction "17_17") (pintype "passive"))
      (node (ref "U1") (pin "18") (pinfunction "GPIO14/RTC_GPIO14/TOUCH14/ADC2_CH3/FSPIWP/FSPIDQS/SUBSPIWP_18") (pintype "passive"))
    )
    (net (code "38") (name "/GPIO15") (class "Default")
      (node (ref "J1") (pin "18") (pinfunction "18_18") (pintype "passive"))
      (node (ref "U1") (pin "19") (pinfunction "GPIO15/RTC_GPIO15/U0RTS/ADC2_CH4/XTAL_32K_P_19") (pintype "passive"))
    )
    (net (code "39") (name "/GPIO16") (class "Default")
      (node (ref "J1") (pin "19") (pinfunction "19_19") (pintype "passive"))
      (node (ref "U1") (pin "20") (pinfunction "GPIO16/RTC_GPIO16/U0CTS/ADC2_CH5/XTAL_32K_N_20") (pintype "passive"))
    )
    (net (code "40") (name "/GPIO17") (class "Default")
      (node (ref "J1") (pin "20") (pinfunction "20_20") (pintype "passive"))
      (node (ref "U1") (pin "21") (pinfunction "GPIO17/RTC_GPIO17/U1TXD/ADC2_CH6_21") (pintype "passive"))
    )
    (net (code "41") (name "/GPIO18") (class "Default")
      (node (ref "J1") (pin "21") (pinfunction "21_21") (pintype "passive"))
      (node (ref "U1") (pin "22") (pinfunction "GPIO18/RTC_GPIO18/U1RXD/ADC2_CH7/CLK_OUT3_22") (pintype "passive"))
    )
    (net (code "42") (name "/GPIO21") (class "Default")
      (node (ref "J2") (pin "19") (pinfunction "19_19") (pintype "passive"))
      (node (ref "U1") (pin "25") (pinfunction "GPIO21/RTC_GPIO21_25") (pintype "passive"))
    )
    (net (code "43") (name "/GPIO26") (class "Default")
      (node (ref "J2") (pin "18") (pinfunction "18_18") (pintype "passive"))
      (node (ref "U1") (pin "26") (pinfunction "GPIO26/SPICS1_26") (pintype "passive"))
    )
    (net (code "44") (name "/GPIO33") (class "Default")
      (node (ref "J2") (pin "17") (pinfunction "17_17") (pintype "passive"))
      (node (ref "U1") (pin "28") (pinfunction "GPIO33/SPIIO4/FSPIHD/SUBSPIHD_28") (pintype "passive"))
    )
    (net (code "45") (name "/GPIO34") (class "Default")
      (node (ref "J2") (pin "16") (pinfunction "16_16") (pintype "passive"))
      (node (ref "U1") (pin "29") (pinfunction "GPIO34/SPIIO5/FSPICS0/SUBSPICS0_29") (pintype "passive"))
    )
    (net (code "46") (name "/GPIO35") (class "Default")
      (node (ref "J2") (pin "15") (pinfunction "15_15") (pintype "passive"))
      (node (ref "U1") (pin "31") (pinfunction "GPIO35/SPIIO6/FSPID/SUBSPID_31") (pintype "passive"))
    )
    (net (code "47") (name "/GPIO36") (class "Default")
      (node (ref "J2") (pin "14") (pinfunction "14_14") (pintype "passive"))
      (node (ref "U1") (pin "32") (pinfunction "GPIO36/SPIIO7/FSPICLK/SUBSPICLK_32") (pintype "passive"))
    )
    (net (code "48") (name "/GPIO37") (class "Default")
      (node (ref "J2") (pin "13") (pinfunction "13_13") (pintype "passive"))
      (node (ref "U1") (pin "33") (pinfunction "GPIO37/SPIDQS/FSPIQ/SUBSPIQ_33") (pintype "passive"))
    )
    (net (code "49") (name "/GPIO38") (class "Default")
      (node (ref "J2") (pin "12") (pinfunction "12_12") (pintype "passive"))
      (node (ref "U1") (pin "34") (pinfunction "GPIO38/FSPIWP/SUBSPIWP_34") (pintype "passive"))
    )
    (net (code "50") (name "/GPIO39") (class "Default")
      (node (ref "J2") (pin "11") (pinfunction "11_11") (pintype "passive"))
      (node (ref "U1") (pin "35") (pinfunction "MTCK/GPIO39/CLK_OUT3/SUBSPICS1_35") (pintype "passive"))
    )
    (net (code "51") (name "/GPIO40") (class "Default")
      (node (ref "J2") (pin "10") (pinfunction "10_10") (pintype "passive"))
      (node (ref "U1") (pin "36") (pinfunction "MTDO/GPIO40/CLK_OUT2_36") (pintype "passive"))
    )
    (net (code "52") (name "/GPIO41") (class "Default")
      (node (ref "J2") (pin "9") (pinfunction "9_9") (pintype "passive"))
      (node (ref "U1") (pin "37") (pinfunction "MTDI/GPIO41/CLK_OUT1_37") (pintype "passive"))
    )
    (net (code "53") (name "/GPIO42") (class "Default")
      (node (ref "J2") (pin "8") (pinfunction "8_8") (pintype "passive"))
      (node (ref "U1") (pin "38") (pinfunction "MTMS/GPIO42_38") (pintype "passive"))
    )
    (net (code "54") (name "/GPIO45") (class "Default")
      (node (ref "J2") (pin "5") (pinfunction "5_5") (pintype "passive"))
      (node (ref "U1") (pin "41") (pinfunction "GPIO45_41") (pintype "passive"))
    )
    (net (code "55") (name "/GPIO46") (class "Default")
      (node (ref "J2") (pin "4") (pinfunction "4_4") (pintype "passive"))
      (node (ref "U1") (pin "44") (pinfunction "GPIO46_44") (pintype "passive"))
    )
    (net (code "56") (name "/GPIO47") (class "Default")
      (node (ref "J2") (pin "23") (pinfunction "23_23") (pintype "passive"))
      (node (ref "U1") (pin "27") (pinfunction "GPIO47/SPICLK_P_DIFF/SUBSPICLK_P_DIFF_27") (pintype "passive"))
    )
    (net (code "57") (name "/GPIO48") (class "Default")
      (node (ref "J2") (pin "22") (pinfunction "22_22") (pintype "passive"))
      (node (ref "U1") (pin "30") (pinfunction "GPIO48/SPICLK_N_DIFF/SUBSPICLK_N_DIFF_30") (pintype "passive"))
    )
    (net (code "58") (name "/RTS_FTDI") (class "Default")
      (node (ref "Q1") (pin "2") (pinfunction "E_2") (pintype "passive"))
      (node (ref "R14") (pin "2") (pinfunction "2_2") (pintype "passive"))
      (node (ref "U2") (pin "19") (pinfunction "~{RTS}_19") (pintype "passive"))
    )
    (net (code "59") (name "/RXD_FTDI") (class "Default")
      (node (ref "R15") (pin "2") (pinfunction "2_2") (pintype "passive"))
      (node (ref "U2") (pin "1") (pinfunction "RXD_1") (pintype "passive"))
    )
    (net (code "60") (name "/TXD_FTDI") (class "Default")
      (node (ref "R16") (pin "2") (pinfunction "2_2") (pintype "passive"))
      (node (ref "U2") (pin "17") (pinfunction "TXD_17") (pintype "passive"))
    )
    (net (code "61") (name "/U0RXD") (class "Default")
      (node (ref "J2") (pin "6") (pinfunction "6_6") (pintype "passive"))
      (node (ref "R16") (pin "1") (pinfunction "1_1") (pintype "passive"))
      (node (ref "U1") (pin "40") (pinfunction "U0RXD/GPIO44/CLK_OUT2_40") (pintype "passive"))
    )
    (net (code "62") (name "/U0TXD") (class "Default")
      (node (ref "J2") (pin "7") (pinfunction "7_7") (pintype "passive"))
      (node (ref "R15") (pin "1") (pinfunction "1_1") (pintype "passive"))
      (node (ref "U1") (pin "39") (pinfunction "U0TXD/GPIO43/CLK_OUT1_39") (pintype "passive"))
    )
    (net (code "63") (name "/VBUS_SENSE") (class "Default")
      (node (ref "R10") (pin "1") (pinfunction "1_1") (pintype "passive"))
      (node (ref "R11") (pin "2") (pinfunction "2_2") (pintype "passive"))
      (node (ref "U2") (pin "16") (pinfunction "CBUS3_16") (pintype "passive"))
    )
    (net (code "64") (name "GND") (class "Default")
      (node (ref "C1") (pin "1") (pinfunction "1_1") (pintype "passive"))
      (node (ref "C10") (pin "1") (pinfunction "1_1") (pintype "passive"))
      (node (ref "C11") (pin "1") (pinfunction "1_1") (pintype "passive"))
      (node (ref "C12") (pin "1") (pinfunction "1_1") (pintype "passive"))
      (node (ref "C13") (pin "1") (pinfunction "1_1") (pintype "passive"))
      (node (ref "C14") (pin "1") (pinfunction "1_1") (pintype "passive"))
      (node (ref "C15") (pin "1") (pinfunction "1_1") (pintype "passive"))
      (node (ref "C16") (pin "1") (pinfunction "1_1") (pintype "passive"))
      (node (ref "C17") (pin "1") (pinfunction "1_1") (pintype "passive"))
      (node (ref "C18") (pin "1") (pinfunction "1_1") (pintype "passive"))
      (node (ref "C19") (pin "1") (pinfunction "1_1") (pintype "passive"))
      (node (ref "C2") (pin "1") (pinfunction "1_1") (pintype "passive"))
      (node (ref "C20") (pin "1") (pinfunction "1_1") (pintype "passive"))
      (node (ref "C21") (pin "1") (pinfunction "1_1") (pintype "passive"))
      (node (ref "C3") (pin "1") (pinfunction "1_1") (pintype "passive"))
      (node (ref "C4") (pin "1") (pinfunction "1_1") (pintype "passive"))
      (node (ref "C5") (pin "1") (pinfunction "1_1") (pintype "passive"))
      (node (ref "C6") (pin "1") (pinfunction "1_1") (pintype "passive"))
      (node (ref "C7") (pin "1") (pinfunction "1_1") (pintype "passive"))
      (node (ref "C8") (pin "1") (pinfunction "1_1") (pintype "passive"))
      (node (ref "C9") (pin "1") (pinfunction "1_1") (pintype "passive"))
      (node (ref "D1") (pin "1") (pinfunction "1_1") (pintype "passive"))
      (node (ref "D3") (pin "1") (pinfunction "1_1") (pintype "passive"))
      (node (ref "D4") (pin "1") (pinfunction "1_1") (pintype "passive"))
      (node (ref "D5") (pin "1") (pinfunction "1_1") (pintype "passive"))
      (node (ref "D6") (pin "1") (pinfunction "1_1") (pintype "passive"))
      (node (ref "D7") (pin "1") (pinfunction "1_1") (pintype "passive"))
      (node (ref "D8") (pin "1") (pinfunction "1_1") (pintype "passive"))
      (node (ref "J1") (pin "1") (pinfunction "1_1") (pintype "passive"))
      (node (ref "J1") (pin "23") (pinfunction "23_23") (pintype "passive"))
      (node (ref "J2") (pin "2") (pinfunction "2_2") (pintype "passive"))
      (node (ref "J2") (pin "24") (pinfunction "24_24") (pintype "passive"))
      (node (ref "J3") (pin "A1B12") (pinfunction "GND_A1B12_A1B12") (pintype "passive"))
      (node (ref "J3") (pin "B1A12") (pinfunction "GND_B1A12_B1A12") (pintype "passive"))
      (node (ref "J3") (pin "S1") (pinfunction "SHIELD_1_S1") (pintype "passive"))
      (node (ref "J3") (pin "S2") (pinfunction "SHIELD_2_S2") (pintype "passive"))
      (node (ref "J3") (pin "S3") (pinfunction "SHIELD_3_S3") (pintype "passive"))
      (node (ref "J3") (pin "S4") (pinfunction "SHIELD_4_S4") (pintype "passive"))
      (node (ref "J4") (pin "A1B12") (pinfunction "GND_A1B12_A1B12") (pintype "passive"))
      (node (ref "J4") (pin "B1A12") (pinfunction "GND_B1A12_B1A12") (pintype "passive"))
      (node (ref "J4") (pin "S1") (pinfunction "SHIELD_1_S1") (pintype "passive"))
      (node (ref "J4") (pin "S2") (pinfunction "SHIELD_2_S2") (pintype "passive"))
      (node (ref "J4") (pin "S3") (pinfunction "SHIELD_3_S3") (pintype "passive"))
      (node (ref "J4") (pin "S4") (pinfunction "SHIELD_4_S4") (pintype "passive"))
      (node (ref "R11") (pin "1") (pinfunction "1_1") (pintype "passive"))
      (node (ref "R9") (pin "2") (pinfunction "2_2") (pintype "passive"))
      (node (ref "SW1") (pin "3") (pinfunction "3_3") (pintype "passive"))
      (node (ref "SW1") (pin "4") (pinfunction "4_4") (pintype "passive"))
      (node (ref "SW2") (pin "3") (pinfunction "3_3") (pintype "passive"))
      (node (ref "SW2") (pin "4") (pinfunction "4_4") (pintype "passive"))
      (node (ref "U1") (pin "1") (pinfunction "GND_01_1") (pintype "passive"))
      (node (ref "U1") (pin "2") (pinfunction "GND_02_2") (pintype "passive"))
      (node (ref "U1") (pin "42") (pinfunction "GND_42") (pintype "passive"))
      (node (ref "U1") (pin "43") (pinfunction "GND_43") (pintype "passive"))
      (node (ref "U1") (pin "46") (pinfunction "GND_46_46") (pintype "passive"))
      (node (ref "U1") (pin "47") (pinfunction "GND_47_47") (pintype "passive"))
      (node (ref "U1") (pin "48") (pinfunction "GND_48_48") (pintype "passive"))
      (node (ref "U1") (pin "49") (pinfunction "GND_49_49") (pintype "passive"))
      (node (ref "U1") (pin "50") (pinfunction "GND_50_50") (pintype "passive"))
      (node (ref "U1") (pin "51") (pinfunction "GND_51_51") (pintype "passive"))
      (node (ref "U1") (pin "52") (pinfunction "GND_52_52") (pintype "passive"))
      (node (ref "U1") (pin "53") (pinfunction "GND_53_53") (pintype "passive"))
      (node (ref "U1") (pin "54") (pinfunction "GND_54_54") (pintype "passive"))
      (node (ref "U1") (pin "55") (pinfunction "GND_55_55") (pintype "passive"))
      (node (ref "U1") (pin "56") (pinfunction "GND_56_56") (pintype "passive"))
      (node (ref "U1") (pin "57") (pinfunction "GND_57_57") (pintype "passive"))
      (node (ref "U1") (pin "58") (pinfunction "GND_58_58") (pintype "passive"))
      (node (ref "U1") (pin "59") (pinfunction "GND_59_59") (pintype "passive"))
      (node (ref "U1") (pin "60") (pinfunction "GND_60_60") (pintype "passive"))
      (node (ref "U1") (pin "61") (pinfunction "GND_61_61") (pintype "passive"))
      (node (ref "U1") (pin "62") (pinfunction "GND_62_62") (pintype "passive"))
      (node (ref "U1") (pin "63") (pinfunction "GND_63_63") (pintype "passive"))
      (node (ref "U1") (pin "64") (pinfunction "GND_64_64") (pintype "passive"))
      (node (ref "U1") (pin "65") (pinfunction "GND_65_65") (pintype "passive"))
      (node (ref "U1") (pin "66") (pinfunction "GND_66_66") (pintype "passive"))
      (node (ref "U1") (pin "67") (pinfunction "GND_67_67") (pintype "passive"))
      (node (ref "U1") (pin "68") (pinfunction "GND_68_68") (pintype "passive"))
      (node (ref "U1") (pin "69") (pinfunction "GND_69_69") (pintype "passive"))
      (node (ref "U1") (pin "70") (pinfunction "GND_70_70") (pintype "passive"))
      (node (ref "U1") (pin "71") (pinfunction "GND_71_71") (pintype "passive"))
      (node (ref "U1") (pin "72") (pinfunction "GND_72_72") (pintype "passive"))
      (node (ref "U1") (pin "73") (pinfunction "GND_73_73") (pintype "passive"))
      (node (ref "U2") (pin "13") (pinfunction "GND_13") (pintype "passive"))
      (node (ref "U2") (pin "21") (pinfunction "GND_21") (pintype "passive"))
      (node (ref "U2") (pin "3") (pinfunction "GND_3") (pintype "passive"))
      (node (ref "U3") (pin "2") (pinfunction "GND_2") (pintype "power_in"))
      (node (ref "U3") (pin "4") (pinfunction "GND_4") (pintype "power_in"))
    )
    (net (code "65") (name "Net-(D1-Pad2)") (class "Default")
      (node (ref "D1") (pin "2") (pinfunction "2_2") (pintype "passive"))
      (node (ref "R6") (pin "1") (pinfunction "1_1") (pintype "passive"))
    )
    (net (code "66") (name "Net-(D2-Pad2)") (class "Default")
      (node (ref "D2") (pin "2") (pinfunction "2_2") (pintype "passive"))
      (node (ref "R7") (pin "1") (pinfunction "1_1") (pintype "passive"))
    )
    (net (code "67") (name "Net-(J3-CC1)") (class "Default")
      (node (ref "C9") (pin "2") (pinfunction "2_2") (pintype "passive"))
      (node (ref "J3") (pin "A5") (pinfunction "CC1_A5") (pintype "passive"))
    )
    (net (code "68") (name "Net-(J3-CC2)") (class "Default")
      (node (ref "C10") (pin "2") (pinfunction "2_2") (pintype "passive"))
      (node (ref "J3") (pin "B5") (pinfunction "CC2_B5") (pintype "passive"))
    )
    (net (code "69") (name "Net-(J4-CC1)") (class "Default")
      (node (ref "C16") (pin "2") (pinfunction "2_2") (pintype "passive"))
      (node (ref "J4") (pin "A5") (pinfunction "CC1_A5") (pintype "passive"))
    )
    (net (code "70") (name "Net-(J4-CC2)") (class "Default")
      (node (ref "C17") (pin "2") (pinfunction "2_2") (pintype "passive"))
      (node (ref "J4") (pin "B5") (pinfunction "CC2_B5") (pintype "passive"))
    )
    (net (code "71") (name "Net-(Q1-B)") (class "Default")
      (node (ref "Q1") (pin "1") (pinfunction "B_1") (pintype "passive"))
      (node (ref "R12") (pin "1") (pinfunction "1_1") (pintype "passive"))
    )
    (net (code "72") (name "Net-(Q2-B)") (class "Default")
      (node (ref "Q2") (pin "1") (pinfunction "B_1") (pintype "passive"))
      (node (ref "R14") (pin "1") (pinfunction "1_1") (pintype "passive"))
    )
    (net (code "73") (name "Net-(U2-CBUS0)") (class "Default")
      (node (ref "R9") (pin "1") (pinfunction "1_1") (pintype "passive"))
      (node (ref "U2") (pin "15") (pinfunction "CBUS0_15") (pintype "passive"))
    )
    (net (code "74") (name "unconnected-(J1-Pad24)") (class "Default")
      (node (ref "J1") (pin "24") (pinfunction "24_24") (pintype "passive+no_connect"))
    )
    (net (code "75") (name "unconnected-(J3-SBU1-PadA8)") (class "Default")
      (node (ref "J3") (pin "A8") (pinfunction "SBU1_A8") (pintype "passive+no_connect"))
    )
    (net (code "76") (name "unconnected-(J3-SBUS-PadB8)") (class "Default")
      (node (ref "J3") (pin "B8") (pinfunction "SBUS_B8") (pintype "passive+no_connect"))
    )
    (net (code "77") (name "unconnected-(J4-SBU1-PadA8)") (class "Default")
      (node (ref "J4") (pin "A8") (pinfunction "SBU1_A8") (pintype "passive+no_connect"))
    )
    (net (code "78") (name "unconnected-(J4-SBUS-PadB8)") (class "Default")
      (node (ref "J4") (pin "B8") (pinfunction "SBUS_B8") (pintype "passive+no_connect"))
    )
    (net (code "79") (name "unconnected-(U2-CBUS1-Pad14)") (class "Default")
      (node (ref "U2") (pin "14") (pinfunction "CBUS1_14") (pintype "passive+no_connect"))
    )
    (net (code "80") (name "unconnected-(U2-CBUS2-Pad7)") (class "Default")
      (node (ref "U2") (pin "7") (pinfunction "CBUS2_7") (pintype "passive+no_connect"))
    )
    (net (code "81") (name "unconnected-(U2-~{CTS}-Pad6)") (class "Default")
      (node (ref "U2") (pin "6") (pinfunction "~{CTS}_6") (pintype "passive+no_connect"))
    )
    (net (code "82") (name "unconnected-(U2-~{DCD}-Pad5)") (class "Default")
      (node (ref "U2") (pin "5") (pinfunction "~{DCD}_5") (pintype "passive+no_connect"))
    )
    (net (code "83") (name "unconnected-(U2-~{DSR}-Pad4)") (class "Default")
      (node (ref "U2") (pin "4") (pinfunction "~{DSR}_4") (pintype "passive+no_connect"))
    )
    (net (code "84") (name "unconnected-(U2-~{RI}-Pad2)") (class "Default")
      (node (ref "U2") (pin "2") (pinfunction "~{RI}_2") (pintype "passive+no_connect"))
    )
  )
)
